# AFPGA_VME_IO_banks1_3.net
KiCad netlist of a schematic drawn in Altium Designer
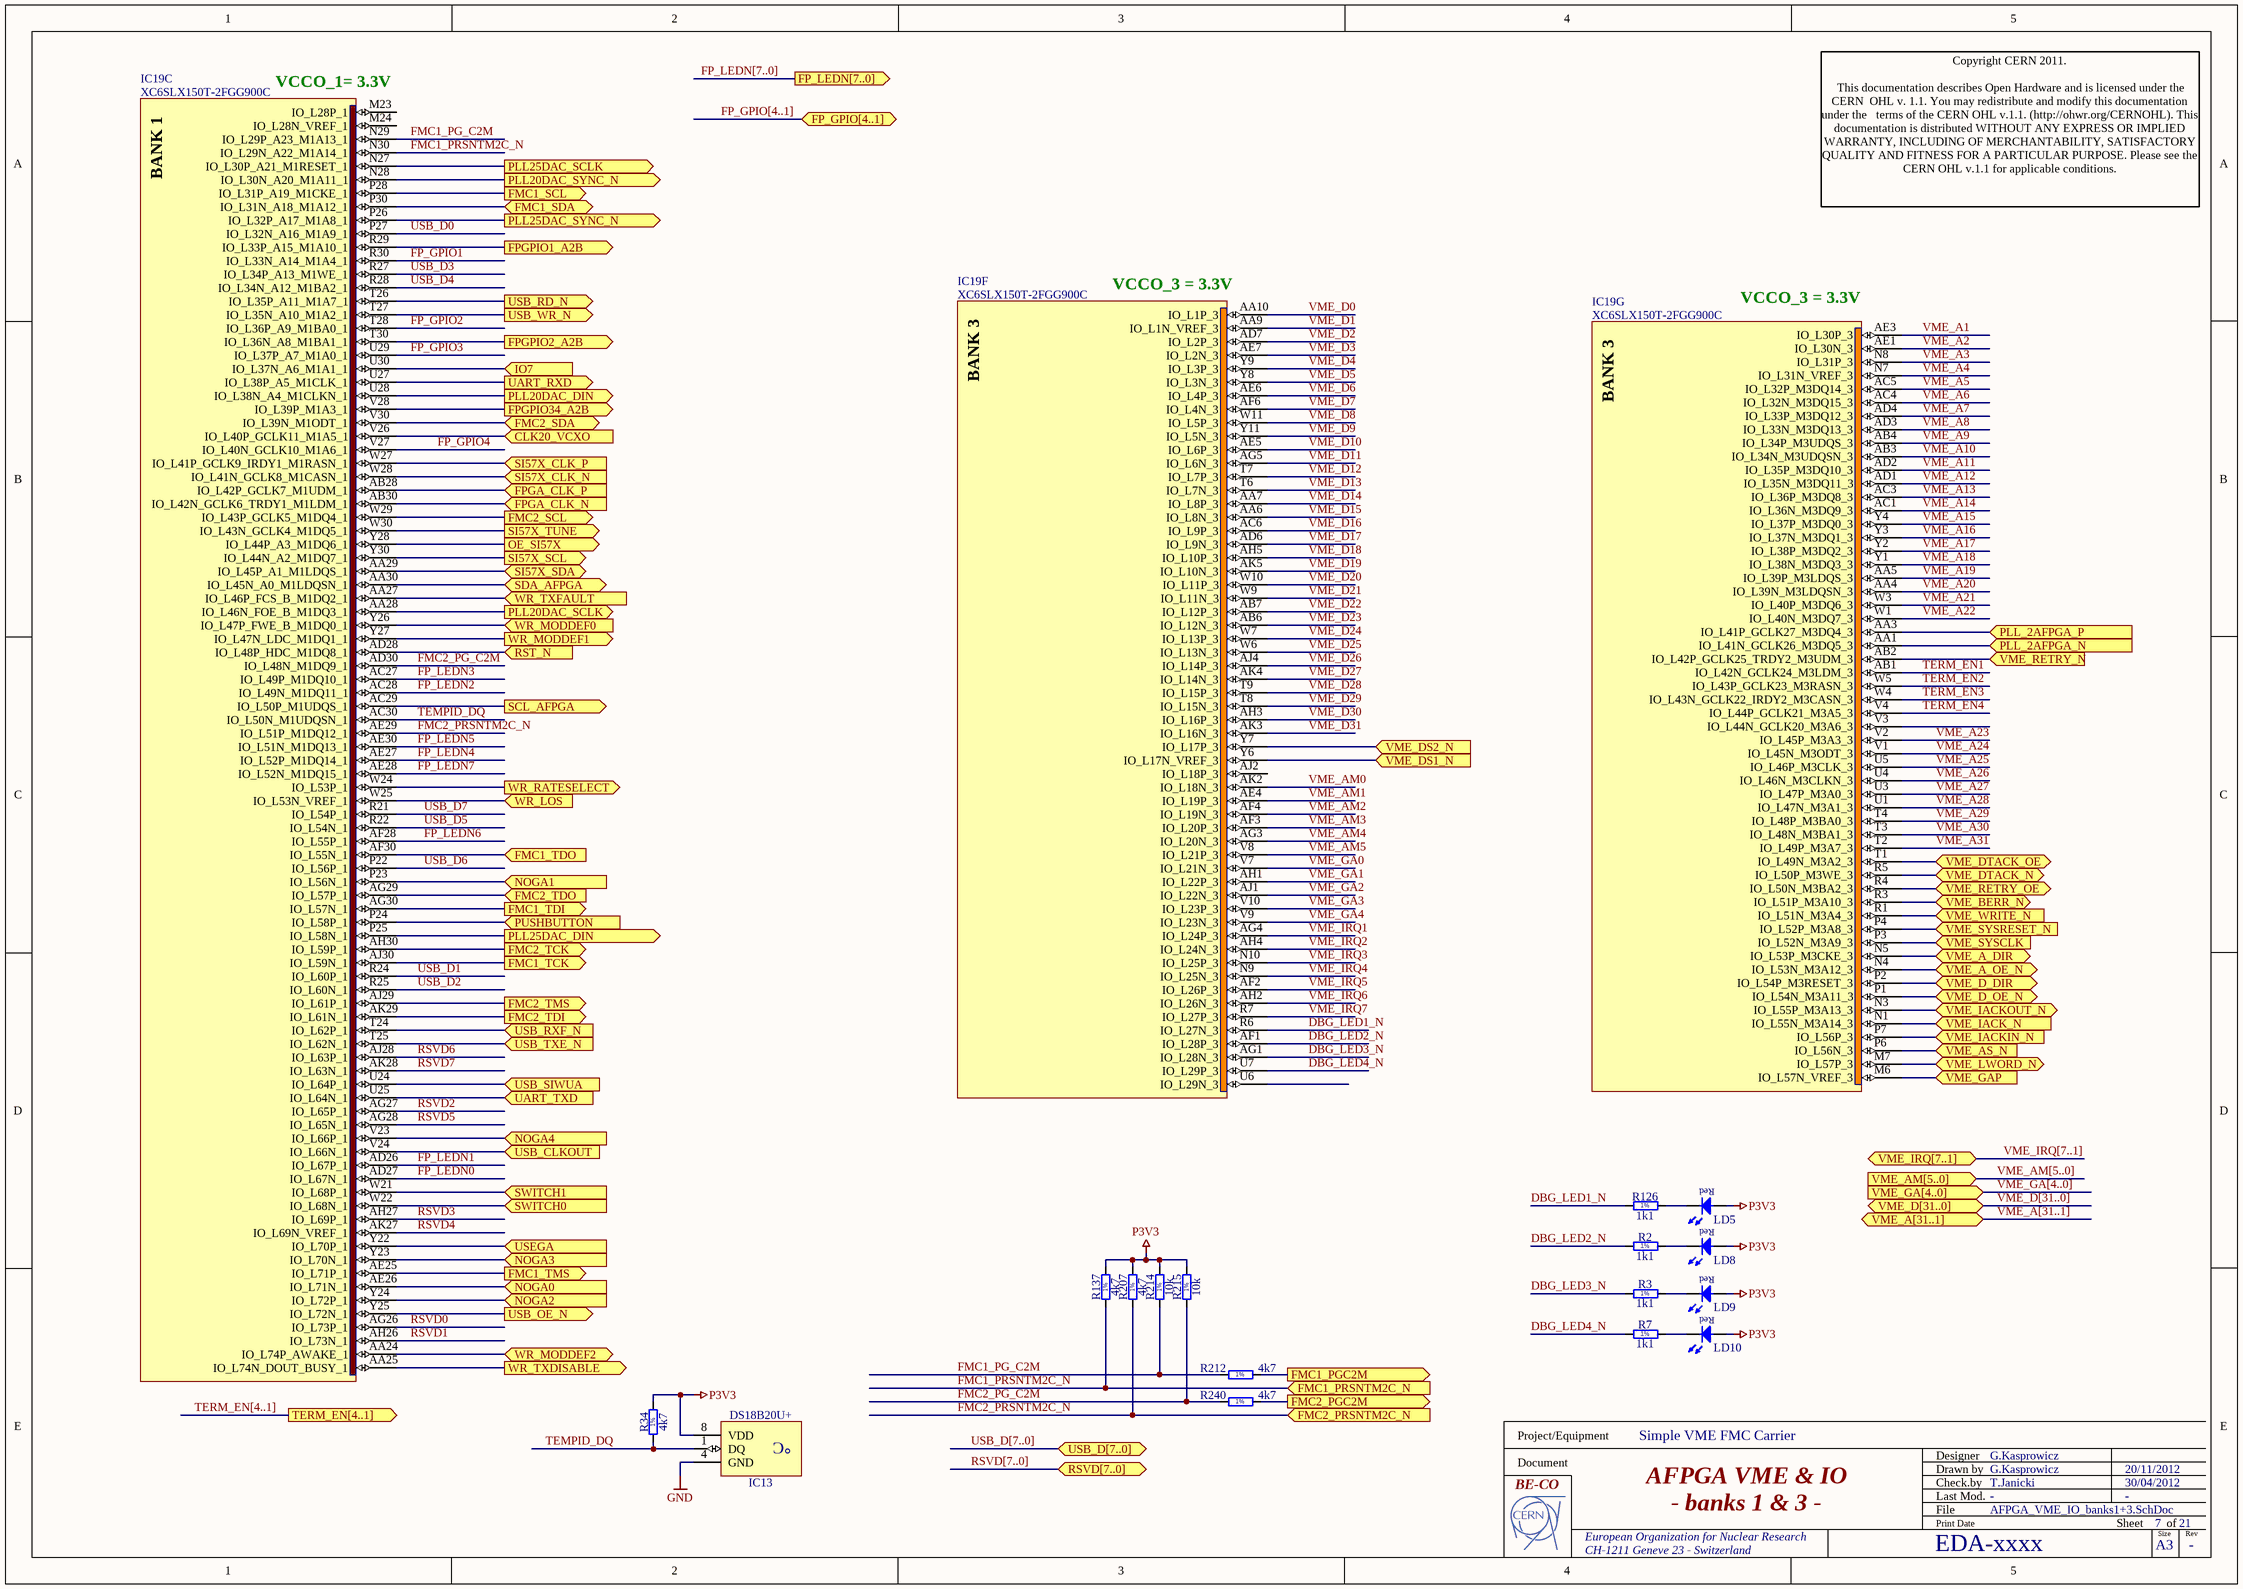
[diagram p0: AFPGA_VME_IO_banks1+3.SchDoc]

(export (version "E")
  (design (tool "Eeschema 10.0.6"))
  (components
    (comp (ref "IC13")
      (value "DS18B20U+")
      (footprint "SOP65P490X110-8N")
      (description "Programmable Resolution 1-Wire Digital Thermometer")
      (fields (field (name "MANUFACTURER") "DALLAS MAXIM") (field (name "AUTHOR") "CERN DEM JLC"))
      (libsource (lib "ICs And Semiconductors") (part "DS18B20U+"))
    )
    (comp (ref "IC19")
      (value "XC6SLX150T-2FGG900C")
      (footprint "BGA900C100P30X30_3100X3100X260")
      (description "SPARTAN-6, FPGA, 900-Ball BGA, Commercial Grade, Pb-Free")
      (fields (field (name "MANUFACTURER") "XILINX") (field (name "AUTHOR") "CERN DEM JLC"))
      (libsource (lib "ICs And Semiconductors") (part "XC6SLX150T-2FGG900C"))
    )
    (comp (ref "LD5")
      (value "Red")
      (footprint "LEDC1608X80N_RED")
      (description "LED Red 1C 2A")
      (fields
        (field (name "PART NUMBER") "LED_ROHM_SML-311UTT86K")
        (field (name "MANUFACTURER") "ROHM")
        (field (name "AUTHOR") "CERN DEM JLC")
      )
      (libsource (lib "ICs And Semiconductors") (part "LED Red 1C 2A"))
    )
    (comp (ref "LD8")
      (value "Red")
      (footprint "LEDC1608X80N_RED")
      (description "LED Red 1C 2A")
      (fields
        (field (name "PART NUMBER") "LED_ROHM_SML-311UTT86K")
        (field (name "MANUFACTURER") "ROHM")
        (field (name "AUTHOR") "CERN DEM JLC")
      )
      (libsource (lib "ICs And Semiconductors") (part "LED Red 1C 2A"))
    )
    (comp (ref "LD9")
      (value "Red")
      (footprint "LEDC1608X80N_RED")
      (description "LED Red 1C 2A")
      (fields
        (field (name "PART NUMBER") "LED_ROHM_SML-311UTT86K")
        (field (name "MANUFACTURER") "ROHM")
        (field (name "AUTHOR") "CERN DEM JLC")
      )
      (libsource (lib "ICs And Semiconductors") (part "LED Red 1C 2A"))
    )
    (comp (ref "LD10")
      (value "Red")
      (footprint "LEDC1608X80N_RED")
      (description "LED Red 1C 2A")
      (fields
        (field (name "PART NUMBER") "LED_ROHM_SML-311UTT86K")
        (field (name "MANUFACTURER") "ROHM")
        (field (name "AUTHOR") "CERN DEM JLC")
      )
      (libsource (lib "ICs And Semiconductors") (part "LED Red 1C 2A"))
    )
    (comp (ref "R2")
      (value "1k1")
      (footprint "RESC1608X55N")
      (description "Resistor - 1%")
      (fields
        (field (name "PART NUMBER") "R0603_1K1_1%_0.1W_100PPM")
        (field (name "POWER") "0.1W")
        (field (name "AUTHOR") "CERN DEM JLC")
      )
      (libsource (lib "Resistors") (part "Resistor - 1%"))
    )
    (comp (ref "R3")
      (value "1k1")
      (footprint "RESC1608X55N")
      (description "Resistor - 1%")
      (fields
        (field (name "PART NUMBER") "R0603_1K1_1%_0.1W_100PPM")
        (field (name "POWER") "0.1W")
        (field (name "AUTHOR") "CERN DEM JLC")
      )
      (libsource (lib "Resistors") (part "Resistor - 1%"))
    )
    (comp (ref "R7")
      (value "1k1")
      (footprint "RESC1608X55N")
      (description "Resistor - 1%")
      (fields
        (field (name "PART NUMBER") "R0603_1K1_1%_0.1W_100PPM")
        (field (name "POWER") "0.1W")
        (field (name "AUTHOR") "CERN DEM JLC")
      )
      (libsource (lib "Resistors") (part "Resistor - 1%"))
    )
    (comp (ref "R34")
      (value "4k7")
      (footprint "RESC1608X55N")
      (description "Resistor - 1%")
      (fields
        (field (name "PART NUMBER") "R0603_4K7_1%_0.1W_100PPM")
        (field (name "POWER") "0.1W")
        (field (name "AUTHOR") "CERN DEM JLC")
      )
      (libsource (lib "Resistors") (part "Resistor - 1%"))
    )
    (comp (ref "R126")
      (value "1k1")
      (footprint "RESC1608X55N")
      (description "Resistor - 1%")
      (fields
        (field (name "PART NUMBER") "R0603_1K1_1%_0.1W_100PPM")
        (field (name "POWER") "0.1W")
        (field (name "AUTHOR") "CERN DEM JLC")
      )
      (libsource (lib "Resistors") (part "Resistor - 1%"))
    )
    (comp (ref "R137")
      (value "4k7")
      (footprint "RESC1608X55N")
      (description "Resistor - 1%")
      (fields
        (field (name "PART NUMBER") "R0603_4K7_1%_0.1W_100PPM")
        (field (name "POWER") "0.1W")
        (field (name "AUTHOR") "CERN DEM JLC")
      )
      (libsource (lib "Resistors") (part "Resistor - 1%"))
    )
    (comp (ref "R207")
      (value "4k7")
      (footprint "RESC1608X55N")
      (description "Resistor - 1%")
      (fields
        (field (name "PART NUMBER") "R0603_4K7_1%_0.1W_100PPM")
        (field (name "POWER") "0.1W")
        (field (name "AUTHOR") "CERN DEM JLC")
      )
      (libsource (lib "Resistors") (part "Resistor - 1%"))
    )
    (comp (ref "R212")
      (value "4k7")
      (footprint "RESC1608X55N")
      (description "Resistor - 1%")
      (fields
        (field (name "PART NUMBER") "R0603_4K7_1%_0.1W_100PPM")
        (field (name "POWER") "0.1W")
        (field (name "AUTHOR") "CERN DEM JLC")
      )
      (libsource (lib "Resistors") (part "Resistor - 1%"))
    )
    (comp (ref "R214")
      (value "10k")
      (footprint "RESC1608X55N")
      (description "Resistor - 1%")
      (fields
        (field (name "PART NUMBER") "R0603_10K_1%_0.1W_100PPM")
        (field (name "POWER") "0.1W")
        (field (name "AUTHOR") "CERN DEM JLC")
      )
      (libsource (lib "Resistors") (part "Resistor - 1%"))
    )
    (comp (ref "R215")
      (value "10k")
      (footprint "RESC1608X55N")
      (description "Resistor - 1%")
      (fields
        (field (name "PART NUMBER") "R0603_10K_1%_0.1W_100PPM")
        (field (name "POWER") "0.1W")
        (field (name "AUTHOR") "CERN DEM JLC")
      )
      (libsource (lib "Resistors") (part "Resistor - 1%"))
    )
    (comp (ref "R240")
      (value "4k7")
      (footprint "RESC1608X55N")
      (description "Resistor - 1%")
      (fields
        (field (name "PART NUMBER") "R0603_4K7_1%_0.1W_100PPM")
        (field (name "POWER") "0.1W")
        (field (name "AUTHOR") "CERN DEM JLC")
      )
      (libsource (lib "Resistors") (part "Resistor - 1%"))
    )
  )
  (nets
    (net (code "1") (name "/CLK20_VCXO") (class "Default")
      (node (ref "IC19") (pin "V26") (pinfunction "IO_L40P_GCLK11_M1A5_1_V26") (pintype "bidirectional"))
    )
    (net (code "2") (name "/DBG_LED1_N") (class "Default")
      (node (ref "IC19") (pin "R6") (pinfunction "IO_L27N_3_R6") (pintype "bidirectional"))
      (node (ref "R126") (pin "1") (pinfunction "1_1") (pintype "passive"))
    )
    (net (code "3") (name "/DBG_LED2_N") (class "Default")
      (node (ref "IC19") (pin "AF1") (pinfunction "IO_L28P_3_AF1") (pintype "bidirectional"))
      (node (ref "R2") (pin "1") (pinfunction "1_1") (pintype "passive"))
    )
    (net (code "4") (name "/DBG_LED3_N") (class "Default")
      (node (ref "IC19") (pin "AG1") (pinfunction "IO_L28N_3_AG1") (pintype "bidirectional"))
      (node (ref "R3") (pin "1") (pinfunction "1_1") (pintype "passive"))
    )
    (net (code "5") (name "/DBG_LED4_N") (class "Default")
      (node (ref "IC19") (pin "U7") (pinfunction "IO_L29P_3_U7") (pintype "bidirectional"))
      (node (ref "R7") (pin "1") (pinfunction "1_1") (pintype "passive"))
    )
    (net (code "6") (name "/FMC1_PGC2M") (class "Default")
      (node (ref "R212") (pin "2") (pinfunction "2_2") (pintype "passive"))
    )
    (net (code "7") (name "/FMC1_PG_C2M") (class "Default")
      (node (ref "IC19") (pin "N29") (pinfunction "IO_L29P_A23_M1A13_1_N29") (pintype "bidirectional"))
      (node (ref "R212") (pin "1") (pinfunction "1_1") (pintype "passive"))
      (node (ref "R214") (pin "1") (pinfunction "1_1") (pintype "passive"))
    )
    (net (code "8") (name "/FMC1_PRSNTM2C_N") (class "Default")
      (node (ref "IC19") (pin "N30") (pinfunction "IO_L29N_A22_M1A14_1_N30") (pintype "bidirectional"))
      (node (ref "R137") (pin "1") (pinfunction "1_1") (pintype "passive"))
    )
    (net (code "9") (name "/FMC1_SCL") (class "Default")
      (node (ref "IC19") (pin "P28") (pinfunction "IO_L31P_A19_M1CKE_1_P28") (pintype "bidirectional"))
    )
    (net (code "10") (name "/FMC1_SDA") (class "Default")
      (node (ref "IC19") (pin "P30") (pinfunction "IO_L31N_A18_M1A12_1_P30") (pintype "bidirectional"))
    )
    (net (code "11") (name "/FMC1_TCK") (class "Default")
      (node (ref "IC19") (pin "AJ30") (pinfunction "IO_L59N_1_AJ30") (pintype "bidirectional"))
    )
    (net (code "12") (name "/FMC1_TDI") (class "Default")
      (node (ref "IC19") (pin "AG30") (pinfunction "IO_L57N_1_AG30") (pintype "bidirectional"))
    )
    (net (code "13") (name "/FMC1_TDO") (class "Default")
      (node (ref "IC19") (pin "AF30") (pinfunction "IO_L55N_1_AF30") (pintype "bidirectional"))
    )
    (net (code "14") (name "/FMC1_TMS") (class "Default")
      (node (ref "IC19") (pin "AE25") (pinfunction "IO_L71P_1_AE25") (pintype "bidirectional"))
    )
    (net (code "15") (name "/FMC2_PGC2M") (class "Default")
      (node (ref "R240") (pin "2") (pinfunction "2_2") (pintype "passive"))
    )
    (net (code "16") (name "/FMC2_PG_C2M") (class "Default")
      (node (ref "IC19") (pin "AD30") (pinfunction "IO_L48N_M1DQ9_1_AD30") (pintype "bidirectional"))
      (node (ref "R215") (pin "1") (pinfunction "1_1") (pintype "passive"))
      (node (ref "R240") (pin "1") (pinfunction "1_1") (pintype "passive"))
    )
    (net (code "17") (name "/FMC2_PRSNTM2C_N") (class "Default")
      (node (ref "IC19") (pin "AE29") (pinfunction "IO_L51P_M1DQ12_1_AE29") (pintype "bidirectional"))
      (node (ref "R207") (pin "1") (pinfunction "1_1") (pintype "passive"))
    )
    (net (code "18") (name "/FMC2_SCL") (class "Default")
      (node (ref "IC19") (pin "W29") (pinfunction "IO_L43P_GCLK5_M1DQ4_1_W29") (pintype "bidirectional"))
    )
    (net (code "19") (name "/FMC2_SDA") (class "Default")
      (node (ref "IC19") (pin "V30") (pinfunction "IO_L39N_M1ODT_1_V30") (pintype "bidirectional"))
    )
    (net (code "20") (name "/FMC2_TCK") (class "Default")
      (node (ref "IC19") (pin "AH30") (pinfunction "IO_L59P_1_AH30") (pintype "bidirectional"))
    )
    (net (code "21") (name "/FMC2_TDI") (class "Default")
      (node (ref "IC19") (pin "AK29") (pinfunction "IO_L61N_1_AK29") (pintype "bidirectional"))
    )
    (net (code "22") (name "/FMC2_TDO") (class "Default")
      (node (ref "IC19") (pin "AG29") (pinfunction "IO_L57P_1_AG29") (pintype "bidirectional"))
    )
    (net (code "23") (name "/FMC2_TMS") (class "Default")
      (node (ref "IC19") (pin "AJ29") (pinfunction "IO_L61P_1_AJ29") (pintype "bidirectional"))
    )
    (net (code "24") (name "/FPGA_CLK_N") (class "Default")
      (node (ref "IC19") (pin "AB30") (pinfunction "IO_L42N_GCLK6_TRDY1_M1LDM_1_AB30") (pintype "bidirectional"))
    )
    (net (code "25") (name "/FPGA_CLK_P") (class "Default")
      (node (ref "IC19") (pin "AB28") (pinfunction "IO_L42P_GCLK7_M1UDM_1_AB28") (pintype "bidirectional"))
    )
    (net (code "26") (name "/FPGPIO1_A2B") (class "Default")
      (node (ref "IC19") (pin "R29") (pinfunction "IO_L33P_A15_M1A10_1_R29") (pintype "bidirectional"))
    )
    (net (code "27") (name "/FPGPIO2_A2B") (class "Default")
      (node (ref "IC19") (pin "T30") (pinfunction "IO_L36N_A8_M1BA1_1_T30") (pintype "bidirectional"))
    )
    (net (code "28") (name "/FPGPIO34_A2B") (class "Default")
      (node (ref "IC19") (pin "V28") (pinfunction "IO_L39P_M1A3_1_V28") (pintype "bidirectional"))
    )
    (net (code "29") (name "/FP_GPIO1") (class "Default")
      (node (ref "IC19") (pin "R30") (pinfunction "IO_L33N_A14_M1A4_1_R30") (pintype "bidirectional"))
    )
    (net (code "30") (name "/FP_GPIO2") (class "Default")
      (node (ref "IC19") (pin "T28") (pinfunction "IO_L36P_A9_M1BA0_1_T28") (pintype "bidirectional"))
    )
    (net (code "31") (name "/FP_GPIO3") (class "Default")
      (node (ref "IC19") (pin "U29") (pinfunction "IO_L37P_A7_M1A0_1_U29") (pintype "bidirectional"))
    )
    (net (code "32") (name "/FP_GPIO4") (class "Default")
      (node (ref "IC19") (pin "V27") (pinfunction "IO_L40N_GCLK10_M1A6_1_V27") (pintype "bidirectional"))
    )
    (net (code "34") (name "/FP_LEDN0") (class "Default")
      (node (ref "IC19") (pin "AD27") (pinfunction "IO_L67N_1_AD27") (pintype "bidirectional"))
    )
    (net (code "35") (name "/FP_LEDN1") (class "Default")
      (node (ref "IC19") (pin "AD26") (pinfunction "IO_L67P_1_AD26") (pintype "bidirectional"))
    )
    (net (code "36") (name "/FP_LEDN2") (class "Default")
      (node (ref "IC19") (pin "AC28") (pinfunction "IO_L49N_M1DQ11_1_AC28") (pintype "bidirectional"))
    )
    (net (code "37") (name "/FP_LEDN3") (class "Default")
      (node (ref "IC19") (pin "AC27") (pinfunction "IO_L49P_M1DQ10_1_AC27") (pintype "bidirectional"))
    )
    (net (code "38") (name "/FP_LEDN4") (class "Default")
      (node (ref "IC19") (pin "AE27") (pinfunction "IO_L52P_M1DQ14_1_AE27") (pintype "bidirectional"))
    )
    (net (code "39") (name "/FP_LEDN5") (class "Default")
      (node (ref "IC19") (pin "AE30") (pinfunction "IO_L51N_M1DQ13_1_AE30") (pintype "bidirectional"))
    )
    (net (code "40") (name "/FP_LEDN6") (class "Default")
      (node (ref "IC19") (pin "AF28") (pinfunction "IO_L55P_1_AF28") (pintype "bidirectional"))
    )
    (net (code "41") (name "/FP_LEDN7") (class "Default")
      (node (ref "IC19") (pin "AE28") (pinfunction "IO_L52N_M1DQ15_1_AE28") (pintype "bidirectional"))
    )
    (net (code "43") (name "/IO7") (class "Default")
      (node (ref "IC19") (pin "U30") (pinfunction "IO_L37N_A6_M1A1_1_U30") (pintype "bidirectional"))
    )
    (net (code "44") (name "/NOGA0") (class "Default")
      (node (ref "IC19") (pin "AE26") (pinfunction "IO_L71N_1_AE26") (pintype "bidirectional"))
    )
    (net (code "45") (name "/NOGA1") (class "Default")
      (node (ref "IC19") (pin "P23") (pinfunction "IO_L56N_1_P23") (pintype "bidirectional"))
    )
    (net (code "46") (name "/NOGA2") (class "Default")
      (node (ref "IC19") (pin "Y24") (pinfunction "IO_L72P_1_Y24") (pintype "bidirectional"))
    )
    (net (code "47") (name "/NOGA3") (class "Default")
      (node (ref "IC19") (pin "Y23") (pinfunction "IO_L70N_1_Y23") (pintype "bidirectional"))
    )
    (net (code "48") (name "/NOGA4") (class "Default")
      (node (ref "IC19") (pin "V23") (pinfunction "IO_L66P_1_V23") (pintype "bidirectional"))
    )
    (net (code "49") (name "/OE_SI57X") (class "Default")
      (node (ref "IC19") (pin "Y28") (pinfunction "IO_L44P_A3_M1DQ6_1_Y28") (pintype "bidirectional"))
    )
    (net (code "50") (name "/PLL20DAC_DIN") (class "Default")
      (node (ref "IC19") (pin "U28") (pinfunction "IO_L38N_A4_M1CLKN_1_U28") (pintype "bidirectional"))
    )
    (net (code "51") (name "/PLL20DAC_SCLK") (class "Default")
      (node (ref "IC19") (pin "AA28") (pinfunction "IO_L46N_FOE_B_M1DQ3_1_AA28") (pintype "bidirectional"))
    )
    (net (code "52") (name "/PLL20DAC_SYNC_N") (class "Default")
      (node (ref "IC19") (pin "N28") (pinfunction "IO_L30N_A20_M1A11_1_N28") (pintype "bidirectional"))
    )
    (net (code "53") (name "/PLL25DAC_DIN") (class "Default")
      (node (ref "IC19") (pin "P25") (pinfunction "IO_L58N_1_P25") (pintype "bidirectional"))
    )
    (net (code "54") (name "/PLL25DAC_SCLK") (class "Default")
      (node (ref "IC19") (pin "N27") (pinfunction "IO_L30P_A21_M1RESET_1_N27") (pintype "bidirectional"))
    )
    (net (code "55") (name "/PLL25DAC_SYNC_N") (class "Default")
      (node (ref "IC19") (pin "P26") (pinfunction "IO_L32P_A17_M1A8_1_P26") (pintype "bidirectional"))
    )
    (net (code "56") (name "/PLL_2AFPGA_N") (class "Default")
      (node (ref "IC19") (pin "AA1") (pinfunction "IO_L41N_GCLK26_M3DQ5_3_AA1") (pintype "bidirectional"))
    )
    (net (code "57") (name "/PLL_2AFPGA_P") (class "Default")
      (node (ref "IC19") (pin "AA3") (pinfunction "IO_L41P_GCLK27_M3DQ4_3_AA3") (pintype "bidirectional"))
    )
    (net (code "58") (name "/PUSHBUTTON") (class "Default")
      (node (ref "IC19") (pin "P24") (pinfunction "IO_L58P_1_P24") (pintype "bidirectional"))
    )
    (net (code "59") (name "/RST_N") (class "Default")
      (node (ref "IC19") (pin "AD28") (pinfunction "IO_L48P_HDC_M1DQ8_1_AD28") (pintype "bidirectional"))
    )
    (net (code "60") (name "/RSVD0") (class "Default")
      (node (ref "IC19") (pin "AG26") (pinfunction "IO_L73P_1_AG26") (pintype "bidirectional"))
    )
    (net (code "61") (name "/RSVD1") (class "Default")
      (node (ref "IC19") (pin "AH26") (pinfunction "IO_L73N_1_AH26") (pintype "bidirectional"))
    )
    (net (code "62") (name "/RSVD2") (class "Default")
      (node (ref "IC19") (pin "AG27") (pinfunction "IO_L65P_1_AG27") (pintype "bidirectional"))
    )
    (net (code "63") (name "/RSVD3") (class "Default")
      (node (ref "IC19") (pin "AH27") (pinfunction "IO_L69P_1_AH27") (pintype "bidirectional"))
    )
    (net (code "64") (name "/RSVD4") (class "Default")
      (node (ref "IC19") (pin "AK27") (pinfunction "IO_L69N_VREF_1_AK27") (pintype "bidirectional"))
    )
    (net (code "65") (name "/RSVD5") (class "Default")
      (node (ref "IC19") (pin "AG28") (pinfunction "IO_L65N_1_AG28") (pintype "bidirectional"))
    )
    (net (code "66") (name "/RSVD6") (class "Default")
      (node (ref "IC19") (pin "AJ28") (pinfunction "IO_L63P_1_AJ28") (pintype "bidirectional"))
    )
    (net (code "67") (name "/RSVD7") (class "Default")
      (node (ref "IC19") (pin "AK28") (pinfunction "IO_L63N_1_AK28") (pintype "bidirectional"))
    )
    (net (code "69") (name "/SCL_AFPGA") (class "Default")
      (node (ref "IC19") (pin "AC29") (pinfunction "IO_L50P_M1UDQS_1_AC29") (pintype "bidirectional"))
    )
    (net (code "70") (name "/SDA_AFPGA") (class "Default")
      (node (ref "IC19") (pin "AA30") (pinfunction "IO_L45N_A0_M1LDQSN_1_AA30") (pintype "bidirectional"))
    )
    (net (code "71") (name "/SI57X_CLK_N") (class "Default")
      (node (ref "IC19") (pin "W28") (pinfunction "IO_L41N_GCLK8_M1CASN_1_W28") (pintype "bidirectional"))
    )
    (net (code "72") (name "/SI57X_CLK_P") (class "Default")
      (node (ref "IC19") (pin "W27") (pinfunction "IO_L41P_GCLK9_IRDY1_M1RASN_1_W27") (pintype "bidirectional"))
    )
    (net (code "73") (name "/SI57X_SCL") (class "Default")
      (node (ref "IC19") (pin "Y30") (pinfunction "IO_L44N_A2_M1DQ7_1_Y30") (pintype "bidirectional"))
    )
    (net (code "74") (name "/SI57X_SDA") (class "Default")
      (node (ref "IC19") (pin "AA29") (pinfunction "IO_L45P_A1_M1LDQS_1_AA29") (pintype "bidirectional"))
    )
    (net (code "75") (name "/SI57X_TUNE") (class "Default")
      (node (ref "IC19") (pin "W30") (pinfunction "IO_L43N_GCLK4_M1DQ5_1_W30") (pintype "bidirectional"))
    )
    (net (code "76") (name "/SWITCH0") (class "Default")
      (node (ref "IC19") (pin "W22") (pinfunction "IO_L68N_1_W22") (pintype "bidirectional"))
    )
    (net (code "77") (name "/SWITCH1") (class "Default")
      (node (ref "IC19") (pin "W21") (pinfunction "IO_L68P_1_W21") (pintype "bidirectional"))
    )
    (net (code "78") (name "/TEMPID_DQ") (class "Default")
      (node (ref "IC13") (pin "1") (pinfunction "DQ_1") (pintype "bidirectional"))
      (node (ref "IC19") (pin "AC30") (pinfunction "IO_L50N_M1UDQSN_1_AC30") (pintype "bidirectional"))
      (node (ref "R34") (pin "1") (pinfunction "1_1") (pintype "passive"))
    )
    (net (code "79") (name "/TERM_EN1") (class "Default")
      (node (ref "IC19") (pin "AB1") (pinfunction "IO_L42N_GCLK24_M3LDM_3_AB1") (pintype "bidirectional"))
    )
    (net (code "80") (name "/TERM_EN2") (class "Default")
      (node (ref "IC19") (pin "W5") (pinfunction "IO_L43P_GCLK23_M3RASN_3_W5") (pintype "bidirectional"))
    )
    (net (code "81") (name "/TERM_EN3") (class "Default")
      (node (ref "IC19") (pin "W4") (pinfunction "IO_L43N_GCLK22_IRDY2_M3CASN_3_W4") (pintype "bidirectional"))
    )
    (net (code "82") (name "/TERM_EN4") (class "Default")
      (node (ref "IC19") (pin "V4") (pinfunction "IO_L44P_GCLK21_M3A5_3_V4") (pintype "bidirectional"))
    )
    (net (code "84") (name "/UART_RXD") (class "Default")
      (node (ref "IC19") (pin "U27") (pinfunction "IO_L38P_A5_M1CLK_1_U27") (pintype "bidirectional"))
    )
    (net (code "85") (name "/UART_TXD") (class "Default")
      (node (ref "IC19") (pin "U25") (pinfunction "IO_L64N_1_U25") (pintype "bidirectional"))
    )
    (net (code "86") (name "/USB_CLKOUT") (class "Default")
      (node (ref "IC19") (pin "V24") (pinfunction "IO_L66N_1_V24") (pintype "bidirectional"))
    )
    (net (code "87") (name "/USB_D0") (class "Default")
      (node (ref "IC19") (pin "P27") (pinfunction "IO_L32N_A16_M1A9_1_P27") (pintype "bidirectional"))
    )
    (net (code "88") (name "/USB_D1") (class "Default")
      (node (ref "IC19") (pin "R24") (pinfunction "IO_L60P_1_R24") (pintype "bidirectional"))
    )
    (net (code "89") (name "/USB_D2") (class "Default")
      (node (ref "IC19") (pin "R25") (pinfunction "IO_L60N_1_R25") (pintype "bidirectional"))
    )
    (net (code "90") (name "/USB_D3") (class "Default")
      (node (ref "IC19") (pin "R27") (pinfunction "IO_L34P_A13_M1WE_1_R27") (pintype "bidirectional"))
    )
    (net (code "91") (name "/USB_D4") (class "Default")
      (node (ref "IC19") (pin "R28") (pinfunction "IO_L34N_A12_M1BA2_1_R28") (pintype "bidirectional"))
    )
    (net (code "92") (name "/USB_D5") (class "Default")
      (node (ref "IC19") (pin "R22") (pinfunction "IO_L54N_1_R22") (pintype "bidirectional"))
    )
    (net (code "93") (name "/USB_D6") (class "Default")
      (node (ref "IC19") (pin "P22") (pinfunction "IO_L56P_1_P22") (pintype "bidirectional"))
    )
    (net (code "94") (name "/USB_D7") (class "Default")
      (node (ref "IC19") (pin "R21") (pinfunction "IO_L54P_1_R21") (pintype "bidirectional"))
    )
    (net (code "96") (name "/USB_OE_N") (class "Default")
      (node (ref "IC19") (pin "Y25") (pinfunction "IO_L72N_1_Y25") (pintype "bidirectional"))
    )
    (net (code "97") (name "/USB_RD_N") (class "Default")
      (node (ref "IC19") (pin "T26") (pinfunction "IO_L35P_A11_M1A7_1_T26") (pintype "bidirectional"))
    )
    (net (code "98") (name "/USB_RXF_N") (class "Default")
      (node (ref "IC19") (pin "T24") (pinfunction "IO_L62P_1_T24") (pintype "bidirectional"))
    )
    (net (code "99") (name "/USB_SIWUA") (class "Default")
      (node (ref "IC19") (pin "U24") (pinfunction "IO_L64P_1_U24") (pintype "bidirectional"))
    )
    (net (code "100") (name "/USB_TXE_N") (class "Default")
      (node (ref "IC19") (pin "T25") (pinfunction "IO_L62N_1_T25") (pintype "bidirectional"))
    )
    (net (code "101") (name "/USB_WR_N") (class "Default")
      (node (ref "IC19") (pin "T27") (pinfunction "IO_L35N_A10_M1A2_1_T27") (pintype "bidirectional"))
    )
    (net (code "102") (name "/USEGA") (class "Default")
      (node (ref "IC19") (pin "Y22") (pinfunction "IO_L70P_1_Y22") (pintype "bidirectional"))
    )
    (net (code "103") (name "/VME_A1") (class "Default")
      (node (ref "IC19") (pin "AE3") (pinfunction "IO_L30P_3_AE3") (pintype "bidirectional"))
    )
    (net (code "104") (name "/VME_A2") (class "Default")
      (node (ref "IC19") (pin "AE1") (pinfunction "IO_L30N_3_AE1") (pintype "bidirectional"))
    )
    (net (code "105") (name "/VME_A3") (class "Default")
      (node (ref "IC19") (pin "N8") (pinfunction "IO_L31P_3_N8") (pintype "bidirectional"))
    )
    (net (code "106") (name "/VME_A4") (class "Default")
      (node (ref "IC19") (pin "N7") (pinfunction "IO_L31N_VREF_3_N7") (pintype "bidirectional"))
    )
    (net (code "107") (name "/VME_A5") (class "Default")
      (node (ref "IC19") (pin "AC5") (pinfunction "IO_L32P_M3DQ14_3_AC5") (pintype "bidirectional"))
    )
    (net (code "108") (name "/VME_A6") (class "Default")
      (node (ref "IC19") (pin "AC4") (pinfunction "IO_L32N_M3DQ15_3_AC4") (pintype "bidirectional"))
    )
    (net (code "109") (name "/VME_A7") (class "Default")
      (node (ref "IC19") (pin "AD4") (pinfunction "IO_L33P_M3DQ12_3_AD4") (pintype "bidirectional"))
    )
    (net (code "110") (name "/VME_A8") (class "Default")
      (node (ref "IC19") (pin "AD3") (pinfunction "IO_L33N_M3DQ13_3_AD3") (pintype "bidirectional"))
    )
    (net (code "111") (name "/VME_A9") (class "Default")
      (node (ref "IC19") (pin "AB4") (pinfunction "IO_L34P_M3UDQS_3_AB4") (pintype "bidirectional"))
    )
    (net (code "112") (name "/VME_A10") (class "Default")
      (node (ref "IC19") (pin "AB3") (pinfunction "IO_L34N_M3UDQSN_3_AB3") (pintype "bidirectional"))
    )
    (net (code "113") (name "/VME_A11") (class "Default")
      (node (ref "IC19") (pin "AD2") (pinfunction "IO_L35P_M3DQ10_3_AD2") (pintype "bidirectional"))
    )
    (net (code "114") (name "/VME_A12") (class "Default")
      (node (ref "IC19") (pin "AD1") (pinfunction "IO_L35N_M3DQ11_3_AD1") (pintype "bidirectional"))
    )
    (net (code "115") (name "/VME_A13") (class "Default")
      (node (ref "IC19") (pin "AC3") (pinfunction "IO_L36P_M3DQ8_3_AC3") (pintype "bidirectional"))
    )
    (net (code "116") (name "/VME_A14") (class "Default")
      (node (ref "IC19") (pin "AC1") (pinfunction "IO_L36N_M3DQ9_3_AC1") (pintype "bidirectional"))
    )
    (net (code "117") (name "/VME_A15") (class "Default")
      (node (ref "IC19") (pin "Y4") (pinfunction "IO_L37P_M3DQ0_3_Y4") (pintype "bidirectional"))
    )
    (net (code "118") (name "/VME_A16") (class "Default")
      (node (ref "IC19") (pin "Y3") (pinfunction "IO_L37N_M3DQ1_3_Y3") (pintype "bidirectional"))
    )
    (net (code "119") (name "/VME_A17") (class "Default")
      (node (ref "IC19") (pin "Y2") (pinfunction "IO_L38P_M3DQ2_3_Y2") (pintype "bidirectional"))
    )
    (net (code "120") (name "/VME_A18") (class "Default")
      (node (ref "IC19") (pin "Y1") (pinfunction "IO_L38N_M3DQ3_3_Y1") (pintype "bidirectional"))
    )
    (net (code "121") (name "/VME_A19") (class "Default")
      (node (ref "IC19") (pin "AA5") (pinfunction "IO_L39P_M3LDQS_3_AA5") (pintype "bidirectional"))
    )
    (net (code "122") (name "/VME_A20") (class "Default")
      (node (ref "IC19") (pin "AA4") (pinfunction "IO_L39N_M3LDQSN_3_AA4") (pintype "bidirectional"))
    )
    (net (code "123") (name "/VME_A21") (class "Default")
      (node (ref "IC19") (pin "W3") (pinfunction "IO_L40P_M3DQ6_3_W3") (pintype "bidirectional"))
    )
    (net (code "124") (name "/VME_A22") (class "Default")
      (node (ref "IC19") (pin "W1") (pinfunction "IO_L40N_M3DQ7_3_W1") (pintype "bidirectional"))
    )
    (net (code "125") (name "/VME_A23") (class "Default")
      (node (ref "IC19") (pin "V2") (pinfunction "IO_L45P_M3A3_3_V2") (pintype "bidirectional"))
    )
    (net (code "126") (name "/VME_A24") (class "Default")
      (node (ref "IC19") (pin "V1") (pinfunction "IO_L45N_M3ODT_3_V1") (pintype "bidirectional"))
    )
    (net (code "127") (name "/VME_A25") (class "Default")
      (node (ref "IC19") (pin "U5") (pinfunction "IO_L46P_M3CLK_3_U5") (pintype "bidirectional"))
    )
    (net (code "128") (name "/VME_A26") (class "Default")
      (node (ref "IC19") (pin "U4") (pinfunction "IO_L46N_M3CLKN_3_U4") (pintype "bidirectional"))
    )
    (net (code "129") (name "/VME_A27") (class "Default")
      (node (ref "IC19") (pin "U3") (pinfunction "IO_L47P_M3A0_3_U3") (pintype "bidirectional"))
    )
    (net (code "130") (name "/VME_A28") (class "Default")
      (node (ref "IC19") (pin "U1") (pinfunction "IO_L47N_M3A1_3_U1") (pintype "bidirectional"))
    )
    (net (code "131") (name "/VME_A29") (class "Default")
      (node (ref "IC19") (pin "T4") (pinfunction "IO_L48P_M3BA0_3_T4") (pintype "bidirectional"))
    )
    (net (code "132") (name "/VME_A30") (class "Default")
      (node (ref "IC19") (pin "T3") (pinfunction "IO_L48N_M3BA1_3_T3") (pintype "bidirectional"))
    )
    (net (code "133") (name "/VME_A31") (class "Default")
      (node (ref "IC19") (pin "T2") (pinfunction "IO_L49P_M3A7_3_T2") (pintype "bidirectional"))
    )
    (net (code "134") (name "/VME_AM0") (class "Default")
      (node (ref "IC19") (pin "AK2") (pinfunction "IO_L18N_3_AK2") (pintype "bidirectional"))
    )
    (net (code "135") (name "/VME_AM1") (class "Default")
      (node (ref "IC19") (pin "AE4") (pinfunction "IO_L19P_3_AE4") (pintype "bidirectional"))
    )
    (net (code "136") (name "/VME_AM2") (class "Default")
      (node (ref "IC19") (pin "AF4") (pinfunction "IO_L19N_3_AF4") (pintype "bidirectional"))
    )
    (net (code "137") (name "/VME_AM3") (class "Default")
      (node (ref "IC19") (pin "AF3") (pinfunction "IO_L20P_3_AF3") (pintype "bidirectional"))
    )
    (net (code "138") (name "/VME_AM4") (class "Default")
      (node (ref "IC19") (pin "AG3") (pinfunction "IO_L20N_3_AG3") (pintype "bidirectional"))
    )
    (net (code "139") (name "/VME_AM5") (class "Default")
      (node (ref "IC19") (pin "V8") (pinfunction "IO_L21P_3_V8") (pintype "bidirectional"))
    )
    (net (code "141") (name "/VME_AS_N") (class "Default")
      (node (ref "IC19") (pin "P6") (pinfunction "IO_L56N_3_P6") (pintype "bidirectional"))
    )
    (net (code "143") (name "/VME_A_DIR") (class "Default")
      (node (ref "IC19") (pin "N5") (pinfunction "IO_L53P_M3CKE_3_N5") (pintype "bidirectional"))
    )
    (net (code "144") (name "/VME_A_OE_N") (class "Default")
      (node (ref "IC19") (pin "N4") (pinfunction "IO_L53N_M3A12_3_N4") (pintype "bidirectional"))
    )
    (net (code "145") (name "/VME_BERR_N") (class "Default")
      (node (ref "IC19") (pin "R3") (pinfunction "IO_L51P_M3A10_3_R3") (pintype "bidirectional"))
    )
    (net (code "146") (name "/VME_D0") (class "Default")
      (node (ref "IC19") (pin "AA10") (pinfunction "IO_L1P_3_AA10") (pintype "bidirectional"))
    )
    (net (code "147") (name "/VME_D1") (class "Default")
      (node (ref "IC19") (pin "AA9") (pinfunction "IO_L1N_VREF_3_AA9") (pintype "bidirectional"))
    )
    (net (code "148") (name "/VME_D2") (class "Default")
      (node (ref "IC19") (pin "AD7") (pinfunction "IO_L2P_3_AD7") (pintype "bidirectional"))
    )
    (net (code "149") (name "/VME_D3") (class "Default")
      (node (ref "IC19") (pin "AE7") (pinfunction "IO_L2N_3_AE7") (pintype "bidirectional"))
    )
    (net (code "150") (name "/VME_D4") (class "Default")
      (node (ref "IC19") (pin "Y9") (pinfunction "IO_L3P_3_Y9") (pintype "bidirectional"))
    )
    (net (code "151") (name "/VME_D5") (class "Default")
      (node (ref "IC19") (pin "Y8") (pinfunction "IO_L3N_3_Y8") (pintype "bidirectional"))
    )
    (net (code "152") (name "/VME_D6") (class "Default")
      (node (ref "IC19") (pin "AE6") (pinfunction "IO_L4P_3_AE6") (pintype "bidirectional"))
    )
    (net (code "153") (name "/VME_D7") (class "Default")
      (node (ref "IC19") (pin "AF6") (pinfunction "IO_L4N_3_AF6") (pintype "bidirectional"))
    )
    (net (code "154") (name "/VME_D8") (class "Default")
      (node (ref "IC19") (pin "W11") (pinfunction "IO_L5P_3_W11") (pintype "bidirectional"))
    )
    (net (code "155") (name "/VME_D9") (class "Default")
      (node (ref "IC19") (pin "Y11") (pinfunction "IO_L5N_3_Y11") (pintype "bidirectional"))
    )
    (net (code "156") (name "/VME_D10") (class "Default")
      (node (ref "IC19") (pin "AE5") (pinfunction "IO_L6P_3_AE5") (pintype "bidirectional"))
    )
    (net (code "157") (name "/VME_D11") (class "Default")
      (node (ref "IC19") (pin "AG5") (pinfunction "IO_L6N_3_AG5") (pintype "bidirectional"))
    )
    (net (code "158") (name "/VME_D12") (class "Default")
      (node (ref "IC19") (pin "T7") (pinfunction "IO_L7P_3_T7") (pintype "bidirectional"))
    )
    (net (code "159") (name "/VME_D13") (class "Default")
      (node (ref "IC19") (pin "T6") (pinfunction "IO_L7N_3_T6") (pintype "bidirectional"))
    )
    (net (code "160") (name "/VME_D14") (class "Default")
      (node (ref "IC19") (pin "AA7") (pinfunction "IO_L8P_3_AA7") (pintype "bidirectional"))
    )
    (net (code "161") (name "/VME_D15") (class "Default")
      (node (ref "IC19") (pin "AA6") (pinfunction "IO_L8N_3_AA6") (pintype "bidirectional"))
    )
    (net (code "162") (name "/VME_D16") (class "Default")
      (node (ref "IC19") (pin "AC6") (pinfunction "IO_L9P_3_AC6") (pintype "bidirectional"))
    )
    (net (code "163") (name "/VME_D17") (class "Default")
      (node (ref "IC19") (pin "AD6") (pinfunction "IO_L9N_3_AD6") (pintype "bidirectional"))
    )
    (net (code "164") (name "/VME_D18") (class "Default")
      (node (ref "IC19") (pin "AH5") (pinfunction "IO_L10P_3_AH5") (pintype "bidirectional"))
    )
    (net (code "165") (name "/VME_D19") (class "Default")
      (node (ref "IC19") (pin "AK5") (pinfunction "IO_L10N_3_AK5") (pintype "bidirectional"))
    )
    (net (code "166") (name "/VME_D20") (class "Default")
      (node (ref "IC19") (pin "W10") (pinfunction "IO_L11P_3_W10") (pintype "bidirectional"))
    )
    (net (code "167") (name "/VME_D21") (class "Default")
      (node (ref "IC19") (pin "W9") (pinfunction "IO_L11N_3_W9") (pintype "bidirectional"))
    )
    (net (code "168") (name "/VME_D22") (class "Default")
      (node (ref "IC19") (pin "AB7") (pinfunction "IO_L12P_3_AB7") (pintype "bidirectional"))
    )
    (net (code "169") (name "/VME_D23") (class "Default")
      (node (ref "IC19") (pin "AB6") (pinfunction "IO_L12N_3_AB6") (pintype "bidirectional"))
    )
    (net (code "170") (name "/VME_D24") (class "Default")
      (node (ref "IC19") (pin "W7") (pinfunction "IO_L13P_3_W7") (pintype "bidirectional"))
    )
    (net (code "171") (name "/VME_D25") (class "Default")
      (node (ref "IC19") (pin "W6") (pinfunction "IO_L13N_3_W6") (pintype "bidirectional"))
    )
    (net (code "172") (name "/VME_D26") (class "Default")
      (node (ref "IC19") (pin "AJ4") (pinfunction "IO_L14P_3_AJ4") (pintype "bidirectional"))
    )
    (net (code "173") (name "/VME_D27") (class "Default")
      (node (ref "IC19") (pin "AK4") (pinfunction "IO_L14N_3_AK4") (pintype "bidirectional"))
    )
    (net (code "174") (name "/VME_D28") (class "Default")
      (node (ref "IC19") (pin "T9") (pinfunction "IO_L15P_3_T9") (pintype "bidirectional"))
    )
    (net (code "175") (name "/VME_D29") (class "Default")
      (node (ref "IC19") (pin "T8") (pinfunction "IO_L15N_3_T8") (pintype "bidirectional"))
    )
    (net (code "176") (name "/VME_D30") (class "Default")
      (node (ref "IC19") (pin "AH3") (pinfunction "IO_L16P_3_AH3") (pintype "bidirectional"))
    )
    (net (code "177") (name "/VME_D31") (class "Default")
      (node (ref "IC19") (pin "AK3") (pinfunction "IO_L16N_3_AK3") (pintype "bidirectional"))
    )
    (net (code "178") (name "/VME_DS1_N") (class "Default")
      (node (ref "IC19") (pin "Y6") (pinfunction "IO_L17N_VREF_3_Y6") (pintype "bidirectional"))
    )
    (net (code "179") (name "/VME_DS2_N") (class "Default")
      (node (ref "IC19") (pin "Y7") (pinfunction "IO_L17P_3_Y7") (pintype "bidirectional"))
    )
    (net (code "180") (name "/VME_DTACK_N") (class "Default")
      (node (ref "IC19") (pin "R5") (pinfunction "IO_L50P_M3WE_3_R5") (pintype "bidirectional"))
    )
    (net (code "181") (name "/VME_DTACK_OE") (class "Default")
      (node (ref "IC19") (pin "T1") (pinfunction "IO_L49N_M3A2_3_T1") (pintype "bidirectional"))
    )
    (net (code "183") (name "/VME_D_DIR") (class "Default")
      (node (ref "IC19") (pin "P2") (pinfunction "IO_L54P_M3RESET_3_P2") (pintype "bidirectional"))
    )
    (net (code "184") (name "/VME_D_OE_N") (class "Default")
      (node (ref "IC19") (pin "P1") (pinfunction "IO_L54N_M3A11_3_P1") (pintype "bidirectional"))
    )
    (net (code "185") (name "/VME_GA0") (class "Default")
      (node (ref "IC19") (pin "V7") (pinfunction "IO_L21N_3_V7") (pintype "bidirectional"))
    )
    (net (code "186") (name "/VME_GA1") (class "Default")
      (node (ref "IC19") (pin "AH1") (pinfunction "IO_L22P_3_AH1") (pintype "bidirectional"))
    )
    (net (code "187") (name "/VME_GA2") (class "Default")
      (node (ref "IC19") (pin "AJ1") (pinfunction "IO_L22N_3_AJ1") (pintype "bidirectional"))
    )
    (net (code "188") (name "/VME_GA3") (class "Default")
      (node (ref "IC19") (pin "V10") (pinfunction "IO_L23P_3_V10") (pintype "bidirectional"))
    )
    (net (code "189") (name "/VME_GA4") (class "Default")
      (node (ref "IC19") (pin "V9") (pinfunction "IO_L23N_3_V9") (pintype "bidirectional"))
    )
    (net (code "190") (name "/VME_GAP") (class "Default")
      (node (ref "IC19") (pin "M6") (pinfunction "IO_L57N_VREF_3_M6") (pintype "bidirectional"))
    )
    (net (code "192") (name "/VME_IACKIN_N") (class "Default")
      (node (ref "IC19") (pin "P7") (pinfunction "IO_L56P_3_P7") (pintype "bidirectional"))
    )
    (net (code "193") (name "/VME_IACKOUT_N") (class "Default")
      (node (ref "IC19") (pin "N3") (pinfunction "IO_L55P_M3A13_3_N3") (pintype "bidirectional"))
    )
    (net (code "194") (name "/VME_IACK_N") (class "Default")
      (node (ref "IC19") (pin "N1") (pinfunction "IO_L55N_M3A14_3_N1") (pintype "bidirectional"))
    )
    (net (code "195") (name "/VME_IRQ1") (class "Default")
      (node (ref "IC19") (pin "AG4") (pinfunction "IO_L24P_3_AG4") (pintype "bidirectional"))
    )
    (net (code "196") (name "/VME_IRQ2") (class "Default")
      (node (ref "IC19") (pin "AH4") (pinfunction "IO_L24N_3_AH4") (pintype "bidirectional"))
    )
    (net (code "197") (name "/VME_IRQ3") (class "Default")
      (node (ref "IC19") (pin "N10") (pinfunction "IO_L25P_3_N10") (pintype "bidirectional"))
    )
    (net (code "198") (name "/VME_IRQ4") (class "Default")
      (node (ref "IC19") (pin "N9") (pinfunction "IO_L25N_3_N9") (pintype "bidirectional"))
    )
    (net (code "199") (name "/VME_IRQ5") (class "Default")
      (node (ref "IC19") (pin "AF2") (pinfunction "IO_L26P_3_AF2") (pintype "bidirectional"))
    )
    (net (code "200") (name "/VME_IRQ6") (class "Default")
      (node (ref "IC19") (pin "AH2") (pinfunction "IO_L26N_3_AH2") (pintype "bidirectional"))
    )
    (net (code "201") (name "/VME_IRQ7") (class "Default")
      (node (ref "IC19") (pin "R7") (pinfunction "IO_L27P_3_R7") (pintype "bidirectional"))
    )
    (net (code "203") (name "/VME_LWORD_N") (class "Default")
      (node (ref "IC19") (pin "M7") (pinfunction "IO_L57P_3_M7") (pintype "bidirectional"))
    )
    (net (code "204") (name "/VME_RETRY_N") (class "Default")
      (node (ref "IC19") (pin "AB2") (pinfunction "IO_L42P_GCLK25_TRDY2_M3UDM_3_AB2") (pintype "bidirectional"))
    )
    (net (code "205") (name "/VME_RETRY_OE") (class "Default")
      (node (ref "IC19") (pin "R4") (pinfunction "IO_L50N_M3BA2_3_R4") (pintype "bidirectional"))
    )
    (net (code "206") (name "/VME_SYSCLK") (class "Default")
      (node (ref "IC19") (pin "P3") (pinfunction "IO_L52N_M3A9_3_P3") (pintype "bidirectional"))
    )
    (net (code "207") (name "/VME_SYSRESET_N") (class "Default")
      (node (ref "IC19") (pin "P4") (pinfunction "IO_L52P_M3A8_3_P4") (pintype "bidirectional"))
    )
    (net (code "208") (name "/VME_WRITE_N") (class "Default")
      (node (ref "IC19") (pin "R1") (pinfunction "IO_L51N_M3A4_3_R1") (pintype "bidirectional"))
    )
    (net (code "209") (name "/WR_LOS") (class "Default")
      (node (ref "IC19") (pin "W25") (pinfunction "IO_L53N_VREF_1_W25") (pintype "bidirectional"))
    )
    (net (code "210") (name "/WR_MODDEF0") (class "Default")
      (node (ref "IC19") (pin "Y26") (pinfunction "IO_L47P_FWE_B_M1DQ0_1_Y26") (pintype "bidirectional"))
    )
    (net (code "211") (name "/WR_MODDEF1") (class "Default")
      (node (ref "IC19") (pin "Y27") (pinfunction "IO_L47N_LDC_M1DQ1_1_Y27") (pintype "bidirectional"))
    )
    (net (code "212") (name "/WR_MODDEF2") (class "Default")
      (node (ref "IC19") (pin "AA24") (pinfunction "IO_L74P_AWAKE_1_AA24") (pintype "bidirectional"))
    )
    (net (code "213") (name "/WR_RATESELECT") (class "Default")
      (node (ref "IC19") (pin "W24") (pinfunction "IO_L53P_1_W24") (pintype "bidirectional"))
    )
    (net (code "214") (name "/WR_TXDISABLE") (class "Default")
      (node (ref "IC19") (pin "AA25") (pinfunction "IO_L74N_DOUT_BUSY_1_AA25") (pintype "bidirectional"))
    )
    (net (code "215") (name "/WR_TXFAULT") (class "Default")
      (node (ref "IC19") (pin "AA27") (pinfunction "IO_L46P_FCS_B_M1DQ2_1_AA27") (pintype "bidirectional"))
    )
    (net (code "216") (name "GND") (class "Default")
      (node (ref "IC13") (pin "4") (pinfunction "GND_4") (pintype "power_in"))
    )
    (net (code "217") (name "Net-(LD5-C)") (class "Default")
      (node (ref "LD5") (pin "1") (pinfunction "C_1") (pintype "passive"))
      (node (ref "R126") (pin "2") (pinfunction "2_2") (pintype "passive"))
    )
    (net (code "218") (name "Net-(LD8-C)") (class "Default")
      (node (ref "LD8") (pin "1") (pinfunction "C_1") (pintype "passive"))
      (node (ref "R2") (pin "2") (pinfunction "2_2") (pintype "passive"))
    )
    (net (code "219") (name "Net-(LD9-C)") (class "Default")
      (node (ref "LD9") (pin "1") (pinfunction "C_1") (pintype "passive"))
      (node (ref "R3") (pin "2") (pinfunction "2_2") (pintype "passive"))
    )
    (net (code "220") (name "Net-(LD10-C)") (class "Default")
      (node (ref "LD10") (pin "1") (pinfunction "C_1") (pintype "passive"))
      (node (ref "R7") (pin "2") (pinfunction "2_2") (pintype "passive"))
    )
    (net (code "221") (name "P3V3") (class "Default")
      (node (ref "IC13") (pin "8") (pinfunction "VDD_8") (pintype "power_in"))
      (node (ref "LD10") (pin "2") (pinfunction "A_2") (pintype "passive"))
      (node (ref "LD5") (pin "2") (pinfunction "A_2") (pintype "passive"))
      (node (ref "LD8") (pin "2") (pinfunction "A_2") (pintype "passive"))
      (node (ref "LD9") (pin "2") (pinfunction "A_2") (pintype "passive"))
      (node (ref "R137") (pin "2") (pinfunction "2_2") (pintype "passive"))
      (node (ref "R207") (pin "2") (pinfunction "2_2") (pintype "passive"))
      (node (ref "R214") (pin "2") (pinfunction "2_2") (pintype "passive"))
      (node (ref "R215") (pin "2") (pinfunction "2_2") (pintype "passive"))
      (node (ref "R34") (pin "2") (pinfunction "2_2") (pintype "passive"))
    )
    (net (code "222") (name "unconnected-(IC19C-IO_L28N_VREF_1-PadM24)") (class "Default")
      (node (ref "IC19") (pin "M24") (pinfunction "IO_L28N_VREF_1_M24") (pintype "bidirectional"))
    )
    (net (code "223") (name "unconnected-(IC19C-IO_L28P_1-PadM23)") (class "Default")
      (node (ref "IC19") (pin "M23") (pinfunction "IO_L28P_1_M23") (pintype "bidirectional"))
    )
    (net (code "224") (name "unconnected-(IC19F-IO_L18P_3-PadAJ2)") (class "Default")
      (node (ref "IC19") (pin "AJ2") (pinfunction "IO_L18P_3_AJ2") (pintype "bidirectional"))
    )
    (net (code "225") (name "unconnected-(IC19F-IO_L29N_3-PadU6)") (class "Default")
      (node (ref "IC19") (pin "U6") (pinfunction "IO_L29N_3_U6") (pintype "bidirectional"))
    )
    (net (code "226") (name "unconnected-(IC19G-IO_L44N_GCLK20_M3A6_3-PadV3)") (class "Default")
      (node (ref "IC19") (pin "V3") (pinfunction "IO_L44N_GCLK20_M3A6_3_V3") (pintype "bidirectional"))
    )
  )
)
